# lpc_ws.net
KiCad netlist of a schematic drawn in Altium Designer
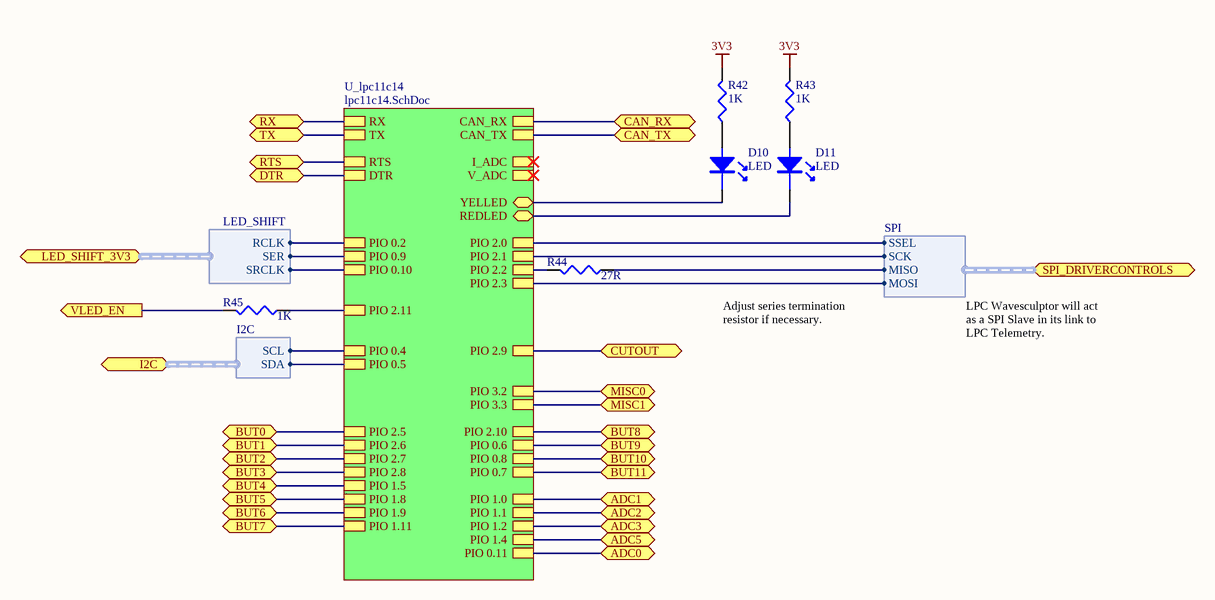
[diagram p0: lpc_ws.SchDoc]

(export (version "E")
  (design (tool "Eeschema 10.0.6"))
  (components
    (comp (ref "D10")
      (value "LED")
      (footprint "0805LED")
      (description "LED CHIPLED 588NM YLW 0805 SMD")
      (fields
        (field (name "MANUFACTURER") "OSRAM Opto Semiconductors Inc")
        (field (name "MANUFACTURER PART NUMBER") "LY R976-PS-36")
      )
      (libsource (lib "RCLDQ") (part "LED"))
    )
    (comp (ref "D11")
      (value "LED")
      (footprint "0805LED")
      (description "LED CHIPLED 633NM RED 0805 SMD")
      (fields
        (field (name "MANUFACTURER") "OSRAM Opto Semiconductors Inc")
        (field (name "MANUFACTURER PART NUMBER") "LS R976-NR-1")
      )
      (libsource (lib "RCLDQ") (part "LED"))
    )
    (comp (ref "R42")
      (value "1K")
      (footprint "0603")
      (description "Resistor")
      (libsource (lib "RCLDQ") (part "RES1"))
    )
    (comp (ref "R43")
      (value "1K")
      (footprint "0603")
      (description "Resistor")
      (libsource (lib "RCLDQ") (part "RES1"))
    )
    (comp (ref "R44")
      (value "27R")
      (footprint "0603")
      (description "Resistor")
      (fields
        (field (name "MANUFACTURER") "Panasonic Electronic Components")
        (field (name "MANUFACTURER PART NUMBER") "ERJ-3EKF27R0V")
      )
      (libsource (lib "RCLDQ") (part "RES1"))
    )
    (comp (ref "R45")
      (value "1K")
      (footprint "0603")
      (description "Resistor")
      (libsource (lib "2009_BatteryMaster") (part "RES1"))
    )
  )
  (nets
    (net (code "28") (name "/MISO") (class "Default")
      (node (ref "R44") (pin "1") (pinfunction "1_1") (pintype "passive"))
    )
    (net (code "30") (name "/PIO 2.2") (class "Default")
      (node (ref "R44") (pin "2") (pinfunction "2_2") (pintype "passive"))
    )
    (net (code "31") (name "/PIO 2.11") (class "Default")
      (node (ref "R45") (pin "1") (pinfunction "1_1") (pintype "passive"))
    )
    (net (code "33") (name "/REDLED") (class "Default")
      (node (ref "D11") (pin "K") (pinfunction "K_K") (pintype "passive"))
    )
    (net (code "43") (name "/VLED_EN") (class "Default")
      (node (ref "R45") (pin "2") (pinfunction "2_2") (pintype "passive"))
    )
    (net (code "45") (name "/YELLED") (class "Default")
      (node (ref "D10") (pin "K") (pinfunction "K_K") (pintype "passive"))
    )
    (net (code "49") (name "3V3") (class "Default")
      (node (ref "R42") (pin "2") (pinfunction "2_2") (pintype "passive"))
      (node (ref "R43") (pin "2") (pinfunction "2_2") (pintype "passive"))
    )
    (net (code "50") (name "Net-(D10-PadA)") (class "Default")
      (node (ref "D10") (pin "A") (pinfunction "A_A") (pintype "passive"))
      (node (ref "R42") (pin "1") (pinfunction "1_1") (pintype "passive"))
    )
    (net (code "51") (name "Net-(D11-PadA)") (class "Default")
      (node (ref "D11") (pin "A") (pinfunction "A_A") (pintype "passive"))
      (node (ref "R43") (pin "1") (pinfunction "1_1") (pintype "passive"))
    )
  )
)
